# carcomputer_split3_bottom1.net
KiCad netlist of a schematic drawn in EAGLE
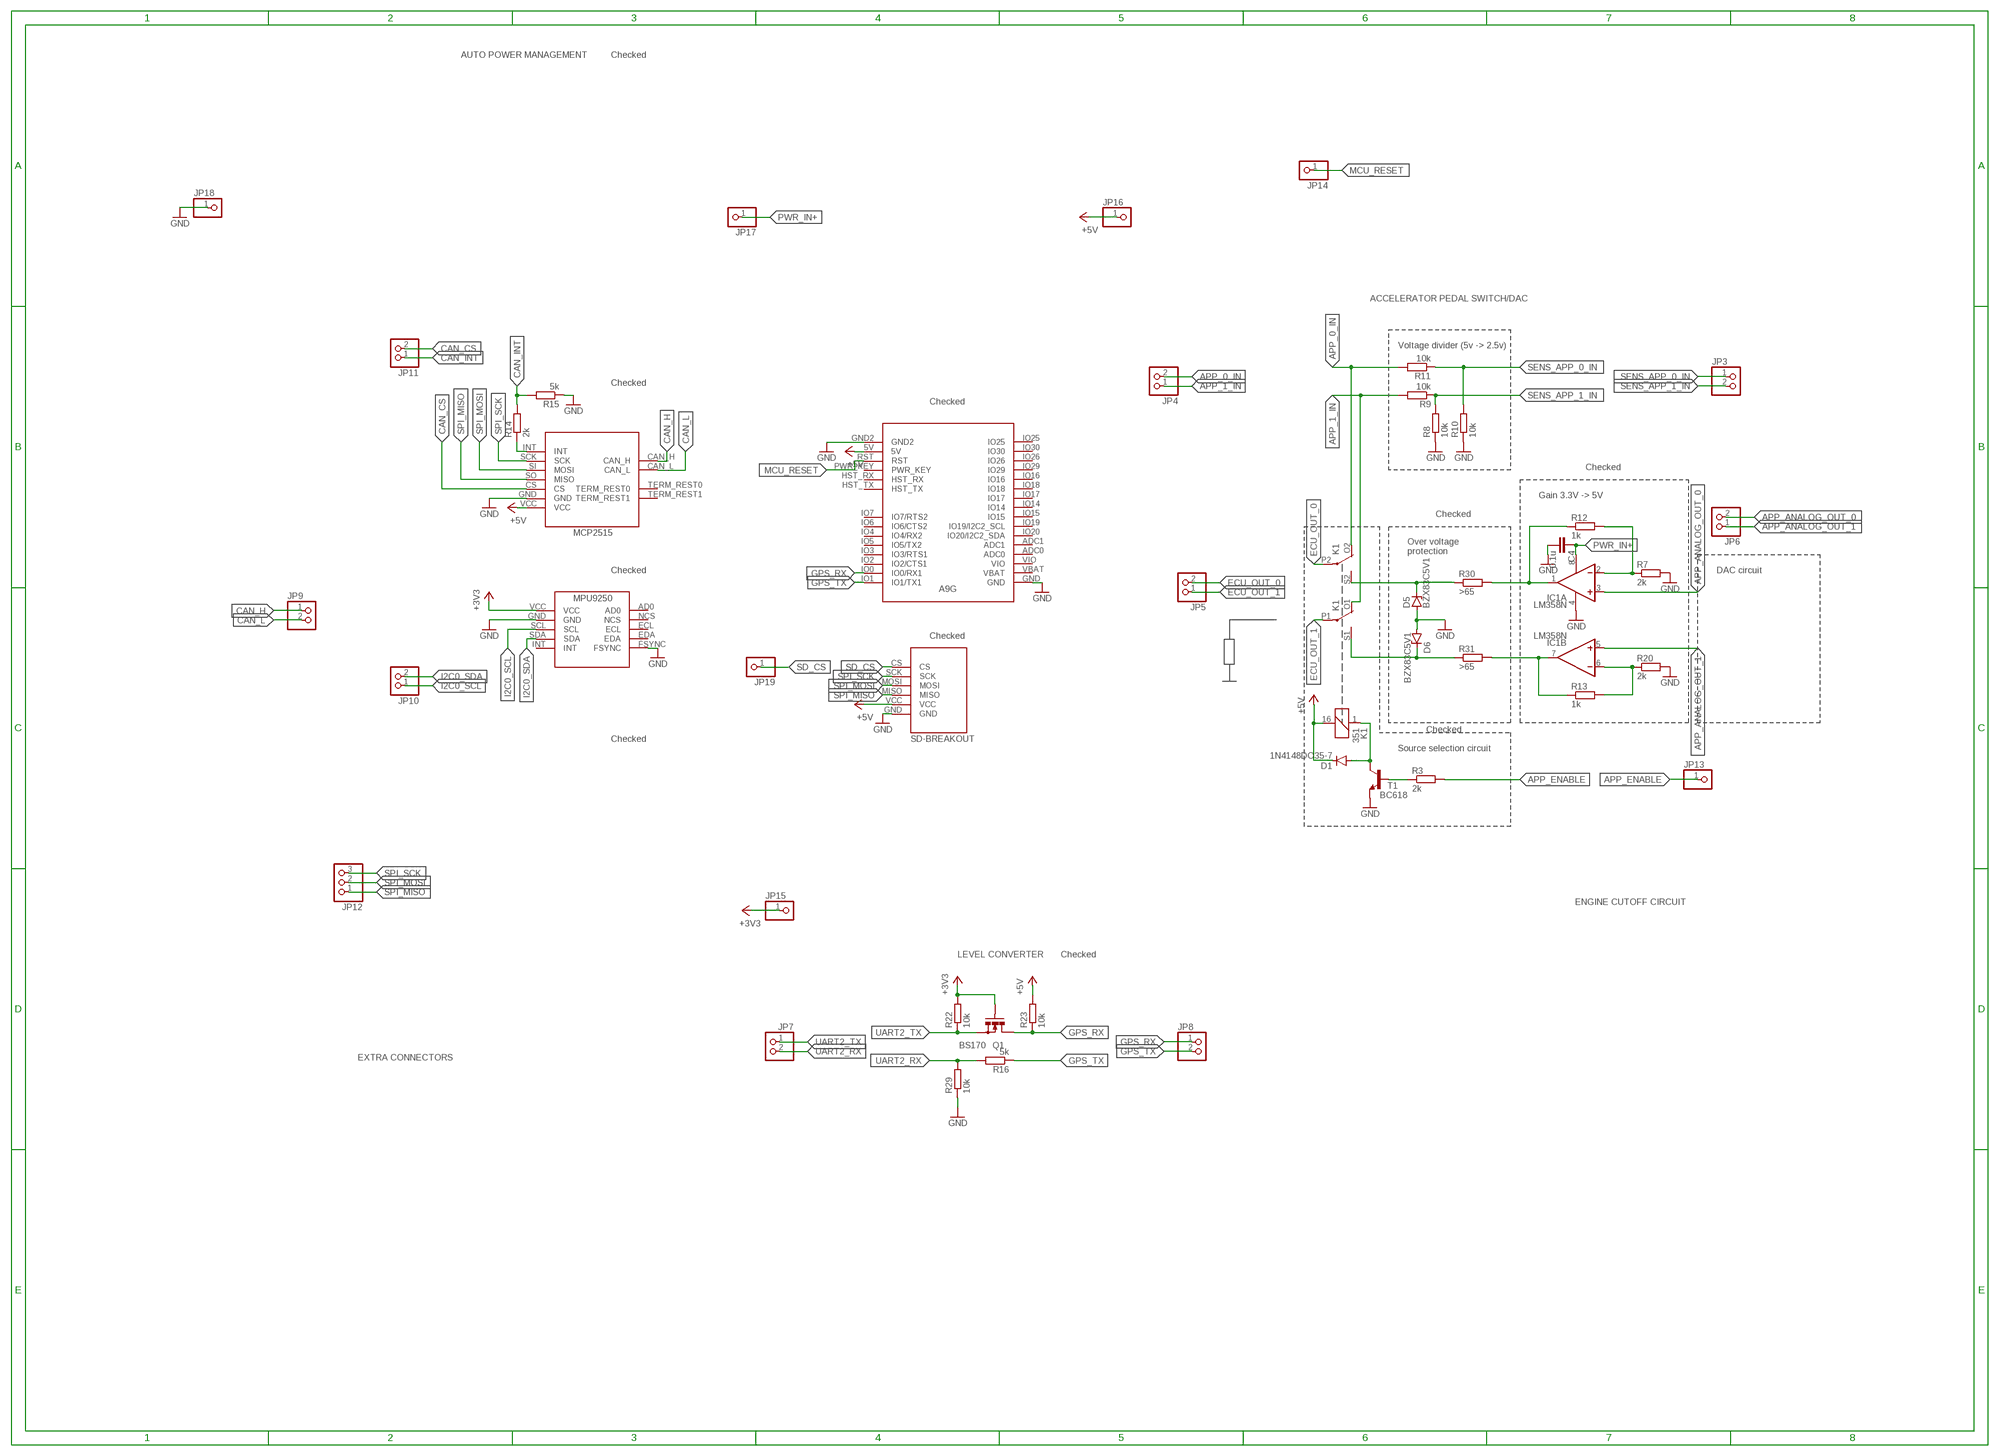
[diagram p0: schematic, sheet 1]

(export (version "E")
  (design (tool "Eeschema 10.0.6"))
  (components
    (comp (ref "C4")
      (value "0.1u")
      (footprint "eagle-import:C025-050X050")
      (libsource (lib "eagle-import") (part "C-EU025-050X050"))
    )
    (comp (ref "D1")
      (value "1N4148DO35-7")
      (footprint "eagle-import:DO35-7")
      (libsource (lib "eagle-import") (part "1N4148DO35-7"))
    )
    (comp (ref "D5")
      (value "BZX83C5V1")
      (footprint "eagle-import:DO41Z10")
      (libsource (lib "eagle-import") (part "BZX85"))
    )
    (comp (ref "D6")
      (value "BZX83C5V1")
      (footprint "eagle-import:DO41Z10")
      (libsource (lib "eagle-import") (part "BZX85"))
    )
    (comp (ref "IC1")
      (value "LM358N")
      (footprint "eagle-import:DIL08")
      (libsource (lib "eagle-import") (part "LM358N"))
    )
    (comp (ref "JP3")
      (value "PINHD-1X2")
      (footprint "eagle-import:1X02")
      (libsource (lib "eagle-import") (part "PINHD-1X2"))
    )
    (comp (ref "JP4")
      (value "PINHD-1X2")
      (footprint "eagle-import:1X02")
      (libsource (lib "eagle-import") (part "PINHD-1X2"))
    )
    (comp (ref "JP5")
      (value "PINHD-1X2")
      (footprint "eagle-import:1X02")
      (libsource (lib "eagle-import") (part "PINHD-1X2"))
    )
    (comp (ref "JP6")
      (value "PINHD-1X2")
      (footprint "eagle-import:1X02")
      (libsource (lib "eagle-import") (part "PINHD-1X2"))
    )
    (comp (ref "JP7")
      (value "PINHD-1X2")
      (footprint "eagle-import:1X02")
      (libsource (lib "eagle-import") (part "PINHD-1X2"))
    )
    (comp (ref "JP8")
      (value "PINHD-1X2")
      (footprint "eagle-import:1X02")
      (libsource (lib "eagle-import") (part "PINHD-1X2"))
    )
    (comp (ref "JP9")
      (value "PINHD-1X2")
      (footprint "eagle-import:1X02")
      (libsource (lib "eagle-import") (part "PINHD-1X2"))
    )
    (comp (ref "JP10")
      (value "PINHD-1X2")
      (footprint "eagle-import:1X02")
      (libsource (lib "eagle-import") (part "PINHD-1X2"))
    )
    (comp (ref "JP11")
      (value "PINHD-1X2")
      (footprint "eagle-import:1X02")
      (libsource (lib "eagle-import") (part "PINHD-1X2"))
    )
    (comp (ref "JP12")
      (value "PINHD-1X3")
      (footprint "eagle-import:1X03")
      (libsource (lib "eagle-import") (part "PINHD-1X3"))
    )
    (comp (ref "JP13")
      (value "PINHD-1X1")
      (footprint "eagle-import:1X01")
      (libsource (lib "eagle-import") (part "PINHD-1X1"))
    )
    (comp (ref "JP14")
      (value "PINHD-1X1")
      (footprint "eagle-import:1X01")
      (libsource (lib "eagle-import") (part "PINHD-1X1"))
    )
    (comp (ref "JP15")
      (value "PINHD-1X1")
      (footprint "eagle-import:1X01")
      (libsource (lib "eagle-import") (part "PINHD-1X1"))
    )
    (comp (ref "JP16")
      (value "PINHD-1X1")
      (footprint "eagle-import:1X01")
      (libsource (lib "eagle-import") (part "PINHD-1X1"))
    )
    (comp (ref "JP17")
      (value "PINHD-1X1")
      (footprint "eagle-import:1X01")
      (libsource (lib "eagle-import") (part "PINHD-1X1"))
    )
    (comp (ref "JP18")
      (value "PINHD-1X1")
      (footprint "eagle-import:1X01")
      (libsource (lib "eagle-import") (part "PINHD-1X1"))
    )
    (comp (ref "JP19")
      (value "PINHD-1X1")
      (footprint "eagle-import:1X01")
      (libsource (lib "eagle-import") (part "PINHD-1X1"))
    )
    (comp (ref "K1")
      (value "351")
      (footprint "eagle-import:351")
      (libsource (lib "eagle-import") (part "351"))
    )
    (comp (ref "Q1")
      (value "BS170")
      (footprint "eagle-import:SOT54E")
      (libsource (lib "eagle-import") (part "BS170"))
    )
    (comp (ref "R3")
      (value "2k")
      (footprint "eagle-import:0207_7")
      (libsource (lib "eagle-import") (part "R-EU_0207/7"))
    )
    (comp (ref "R7")
      (value "2k")
      (footprint "eagle-import:0207_7")
      (libsource (lib "eagle-import") (part "R-EU_0207/7"))
    )
    (comp (ref "R8")
      (value "10k")
      (footprint "eagle-import:0207_7")
      (libsource (lib "eagle-import") (part "R-EU_0207/7"))
    )
    (comp (ref "R9")
      (value "10k")
      (footprint "eagle-import:0207_7")
      (libsource (lib "eagle-import") (part "R-EU_0207/7"))
    )
    (comp (ref "R10")
      (value "10k")
      (footprint "eagle-import:0207_7")
      (libsource (lib "eagle-import") (part "R-EU_0207/7"))
    )
    (comp (ref "R11")
      (value "10k")
      (footprint "eagle-import:0207_7")
      (libsource (lib "eagle-import") (part "R-EU_0207/7"))
    )
    (comp (ref "R12")
      (value "1k")
      (footprint "eagle-import:0207_7")
      (libsource (lib "eagle-import") (part "R-EU_0207/7"))
    )
    (comp (ref "R13")
      (value "1k")
      (footprint "eagle-import:0207_7")
      (libsource (lib "eagle-import") (part "R-EU_0207/7"))
    )
    (comp (ref "R14")
      (value "2k")
      (footprint "eagle-import:0207_7")
      (libsource (lib "eagle-import") (part "R-EU_0207/7"))
    )
    (comp (ref "R15")
      (value "5k")
      (footprint "eagle-import:0207_7")
      (libsource (lib "eagle-import") (part "R-EU_0207/7"))
    )
    (comp (ref "R16")
      (value "5k")
      (footprint "eagle-import:0207_7")
      (libsource (lib "eagle-import") (part "R-EU_0207/7"))
    )
    (comp (ref "R20")
      (value "2k")
      (footprint "eagle-import:0207_7")
      (libsource (lib "eagle-import") (part "R-EU_0207/7"))
    )
    (comp (ref "R22")
      (value "10k")
      (footprint "eagle-import:0207_7")
      (libsource (lib "eagle-import") (part "R-EU_0207/7"))
    )
    (comp (ref "R23")
      (value "10k")
      (footprint "eagle-import:0207_7")
      (libsource (lib "eagle-import") (part "R-EU_0207/7"))
    )
    (comp (ref "R29")
      (value "10k")
      (footprint "eagle-import:0207_7")
      (libsource (lib "eagle-import") (part "R-EU_0207/7"))
    )
    (comp (ref "R30")
      (value ">65")
      (footprint "eagle-import:0207_7")
      (libsource (lib "eagle-import") (part "R-EU_0207/7"))
    )
    (comp (ref "R31")
      (value ">65")
      (footprint "eagle-import:0207_7")
      (libsource (lib "eagle-import") (part "R-EU_0207/7"))
    )
    (comp (ref "T1")
      (value "BC618")
      (footprint "eagle-import:TO92-EBC")
      (libsource (lib "eagle-import") (part "BC618"))
    )
    (comp (ref "U$2")
      (value "MCP2515_DEVBOARDINVERTED")
      (footprint "eagle-import:MCP2515_DEVBOARD_INVERTED")
      (libsource (lib "eagle-import") (part "MCP2515_DEVBOARDINVERTED"))
    )
    (comp (ref "U$3")
      (value "MPU9250_BREAKOUT")
      (footprint "eagle-import:MPU9250_BREAKOUT")
      (libsource (lib "eagle-import") (part "MPU9250_BREAKOUT"))
    )
    (comp (ref "U$5")
      (value "HKD-MICRO-SD-BREAKOUT")
      (footprint "eagle-import:HKD-MICRO-SD-BREAKOUT")
      (libsource (lib "eagle-import") (part "HKD-MICRO-SD-BREAKOUT"))
    )
    (comp (ref "U$6")
      (value "A9G")
      (footprint "eagle-import:A9G")
      (libsource (lib "eagle-import") (part "A9G"))
    )
  )
  (nets
    (net (code "1") (name "+3V3") (class "Default")
      (node (ref "JP15") (pin "1") (pinfunction "1_1") (pintype "passive"))
      (node (ref "Q1") (pin "G") (pinfunction "G_G") (pintype "passive"))
      (node (ref "R22") (pin "2") (pinfunction "2_2") (pintype "passive"))
      (node (ref "U$3") (pin "VCC") (pinfunction "VCC_VCC") (pintype "bidirectional"))
    )
    (net (code "2") (name "+5V") (class "Default")
      (node (ref "D1") (pin "C") (pinfunction "C_C") (pintype "passive"))
      (node (ref "JP16") (pin "1") (pinfunction "1_1") (pintype "passive"))
      (node (ref "K1") (pin "16") (pinfunction "2_16") (pintype "passive"))
      (node (ref "R23") (pin "2") (pinfunction "2_2") (pintype "passive"))
      (node (ref "U$2") (pin "VCC") (pinfunction "VCC_VCC") (pintype "bidirectional"))
      (node (ref "U$5") (pin "VCC") (pinfunction "VCC_VCC") (pintype "bidirectional"))
      (node (ref "U$6") (pin "5V") (pinfunction "5V_5V") (pintype "bidirectional"))
    )
    (net (code "3") (name "APP_0_IN") (class "Default")
      (node (ref "JP4") (pin "2") (pinfunction "2_2") (pintype "passive"))
      (node (ref "K1") (pin "O2") (pinfunction "O_O2") (pintype "passive"))
      (node (ref "R11") (pin "2") (pinfunction "2_2") (pintype "passive"))
    )
    (net (code "4") (name "APP_1_IN") (class "Default")
      (node (ref "JP4") (pin "1") (pinfunction "1_1") (pintype "passive"))
      (node (ref "K1") (pin "O1") (pinfunction "O_O1") (pintype "passive"))
      (node (ref "R9") (pin "2") (pinfunction "2_2") (pintype "passive"))
    )
    (net (code "5") (name "APP_ANALOG_OUT_0") (class "Default")
      (node (ref "IC1") (pin "3") (pinfunction "+IN_3") (pintype "input"))
      (node (ref "JP6") (pin "2") (pinfunction "2_2") (pintype "passive"))
    )
    (net (code "6") (name "APP_ANALOG_OUT_1") (class "Default")
      (node (ref "IC1") (pin "5") (pinfunction "+IN_5") (pintype "input"))
      (node (ref "JP6") (pin "1") (pinfunction "1_1") (pintype "passive"))
    )
    (net (code "7") (name "APP_ENABLE") (class "Default")
      (node (ref "JP13") (pin "1") (pinfunction "1_1") (pintype "passive"))
      (node (ref "R3") (pin "2") (pinfunction "2_2") (pintype "passive"))
    )
    (net (code "8") (name "CAN_CS") (class "Default")
      (node (ref "JP11") (pin "2") (pinfunction "2_2") (pintype "passive"))
      (node (ref "U$2") (pin "CS") (pinfunction "CS_CS") (pintype "input"))
    )
    (net (code "9") (name "CAN_H") (class "Default")
      (node (ref "JP9") (pin "1") (pinfunction "1_1") (pintype "passive"))
      (node (ref "U$2") (pin "CAN_H") (pinfunction "CAN_H_CAN_H") (pintype "bidirectional"))
    )
    (net (code "10") (name "CAN_INT") (class "Default")
      (node (ref "JP11") (pin "1") (pinfunction "1_1") (pintype "passive"))
      (node (ref "R14") (pin "2") (pinfunction "2_2") (pintype "passive"))
      (node (ref "R15") (pin "2") (pinfunction "2_2") (pintype "passive"))
    )
    (net (code "11") (name "CAN_L") (class "Default")
      (node (ref "JP9") (pin "2") (pinfunction "2_2") (pintype "passive"))
      (node (ref "U$2") (pin "CAN_L") (pinfunction "CAN_L_CAN_L") (pintype "bidirectional"))
    )
    (net (code "12") (name "ECU_OUT_0") (class "Default")
      (node (ref "JP5") (pin "2") (pinfunction "2_2") (pintype "passive"))
      (node (ref "K1") (pin "P2") (pinfunction "P_P2") (pintype "passive"))
    )
    (net (code "13") (name "ECU_OUT_1") (class "Default")
      (node (ref "JP5") (pin "1") (pinfunction "1_1") (pintype "passive"))
      (node (ref "K1") (pin "P1") (pinfunction "P_P1") (pintype "passive"))
    )
    (net (code "14") (name "GND") (class "Default")
      (node (ref "C4") (pin "2") (pinfunction "2_2") (pintype "passive"))
      (node (ref "D5") (pin "A") (pinfunction "A_A") (pintype "passive"))
      (node (ref "D6") (pin "A") (pinfunction "A_A") (pintype "passive"))
      (node (ref "IC1") (pin "4") (pinfunction "V-_4") (pintype "power_in"))
      (node (ref "JP18") (pin "1") (pinfunction "1_1") (pintype "passive"))
      (node (ref "R10") (pin "1") (pinfunction "1_1") (pintype "passive"))
      (node (ref "R15") (pin "1") (pinfunction "1_1") (pintype "passive"))
      (node (ref "R20") (pin "2") (pinfunction "2_2") (pintype "passive"))
      (node (ref "R29") (pin "1") (pinfunction "1_1") (pintype "passive"))
      (node (ref "R7") (pin "2") (pinfunction "2_2") (pintype "passive"))
      (node (ref "R8") (pin "1") (pinfunction "1_1") (pintype "passive"))
      (node (ref "T1") (pin "E") (pinfunction "E_E") (pintype "passive"))
      (node (ref "U$2") (pin "GND") (pinfunction "GND_GND") (pintype "bidirectional"))
      (node (ref "U$3") (pin "FSYNC") (pinfunction "FSYNC_FSYNC") (pintype "bidirectional"))
      (node (ref "U$3") (pin "GND") (pinfunction "GND_GND") (pintype "bidirectional"))
      (node (ref "U$5") (pin "GND") (pinfunction "GND_GND") (pintype "bidirectional"))
      (node (ref "U$6") (pin "GND") (pinfunction "GND_GND") (pintype "bidirectional"))
      (node (ref "U$6") (pin "GND2") (pinfunction "GND2_GND2") (pintype "bidirectional"))
    )
    (net (code "15") (name "GPS_RX") (class "Default")
      (node (ref "JP8") (pin "1") (pinfunction "1_1") (pintype "passive"))
      (node (ref "Q1") (pin "D") (pinfunction "D_D") (pintype "passive"))
      (node (ref "R23") (pin "1") (pinfunction "1_1") (pintype "passive"))
      (node (ref "U$6") (pin "IO0") (pinfunction "IO0/RX1_IO0") (pintype "bidirectional"))
    )
    (net (code "16") (name "GPS_TX") (class "Default")
      (node (ref "JP8") (pin "2") (pinfunction "2_2") (pintype "passive"))
      (node (ref "R16") (pin "1") (pinfunction "1_1") (pintype "passive"))
      (node (ref "U$6") (pin "IO1") (pinfunction "IO1/TX1_IO1") (pintype "bidirectional"))
    )
    (net (code "17") (name "I2C0_SCL") (class "Default")
      (node (ref "JP10") (pin "1") (pinfunction "1_1") (pintype "passive"))
      (node (ref "U$3") (pin "SCL") (pinfunction "SCL_SCL") (pintype "bidirectional"))
    )
    (net (code "18") (name "I2C0_SDA") (class "Default")
      (node (ref "JP10") (pin "2") (pinfunction "2_2") (pintype "passive"))
      (node (ref "U$3") (pin "SDA") (pinfunction "SDA_SDA") (pintype "bidirectional"))
    )
    (net (code "19") (name "MCU_RESET") (class "Default")
      (node (ref "JP14") (pin "1") (pinfunction "1_1") (pintype "passive"))
      (node (ref "U$6") (pin "RST") (pinfunction "RST_RST") (pintype "bidirectional"))
    )
    (net (code "20") (name "Net-(D1-PadA)") (class "Default")
      (node (ref "D1") (pin "A") (pinfunction "A_A") (pintype "passive"))
      (node (ref "K1") (pin "1") (pinfunction "1_1") (pintype "passive"))
      (node (ref "T1") (pin "C") (pinfunction "C_C") (pintype "passive"))
    )
    (net (code "21") (name "Net-(IC1A--IN)") (class "Default")
      (node (ref "IC1") (pin "2") (pinfunction "-IN_2") (pintype "input"))
      (node (ref "R12") (pin "2") (pinfunction "2_2") (pintype "passive"))
      (node (ref "R7") (pin "1") (pinfunction "1_1") (pintype "passive"))
    )
    (net (code "22") (name "Net-(IC1A-OUT)") (class "Default")
      (node (ref "IC1") (pin "1") (pinfunction "OUT_1") (pintype "output"))
      (node (ref "R12") (pin "1") (pinfunction "1_1") (pintype "passive"))
      (node (ref "R30") (pin "2") (pinfunction "2_2") (pintype "passive"))
    )
    (net (code "23") (name "Net-(IC1B--IN)") (class "Default")
      (node (ref "IC1") (pin "6") (pinfunction "-IN_6") (pintype "input"))
      (node (ref "R13") (pin "2") (pinfunction "2_2") (pintype "passive"))
      (node (ref "R20") (pin "1") (pinfunction "1_1") (pintype "passive"))
    )
    (net (code "24") (name "Net-(IC1B-OUT)") (class "Default")
      (node (ref "IC1") (pin "7") (pinfunction "OUT_7") (pintype "output"))
      (node (ref "R13") (pin "1") (pinfunction "1_1") (pintype "passive"))
      (node (ref "R31") (pin "2") (pinfunction "2_2") (pintype "passive"))
    )
    (net (code "25") (name "Net-(K1B-S)") (class "Default")
      (node (ref "D6") (pin "C") (pinfunction "C_C") (pintype "passive"))
      (node (ref "K1") (pin "S1") (pinfunction "S_S1") (pintype "passive"))
      (node (ref "R31") (pin "1") (pinfunction "1_1") (pintype "passive"))
    )
    (net (code "26") (name "Net-(K1C-S)") (class "Default")
      (node (ref "D5") (pin "C") (pinfunction "C_C") (pintype "passive"))
      (node (ref "K1") (pin "S2") (pinfunction "S_S2") (pintype "passive"))
      (node (ref "R30") (pin "1") (pinfunction "1_1") (pintype "passive"))
    )
    (net (code "27") (name "Net-(R3-Pad1)") (class "Default")
      (node (ref "R3") (pin "1") (pinfunction "1_1") (pintype "passive"))
      (node (ref "T1") (pin "B") (pinfunction "B_B") (pintype "passive"))
    )
    (net (code "28") (name "Net-(R14-Pad1)") (class "Default")
      (node (ref "R14") (pin "1") (pinfunction "1_1") (pintype "passive"))
      (node (ref "U$2") (pin "INT") (pinfunction "INT_INT") (pintype "output"))
    )
    (net (code "29") (name "PWR_IN+") (class "Default")
      (node (ref "C4") (pin "1") (pinfunction "1_1") (pintype "passive"))
      (node (ref "IC1") (pin "8") (pinfunction "V+_8") (pintype "power_in"))
      (node (ref "JP17") (pin "1") (pinfunction "1_1") (pintype "passive"))
    )
    (net (code "30") (name "SD_CS") (class "Default")
      (node (ref "JP19") (pin "1") (pinfunction "1_1") (pintype "passive"))
      (node (ref "U$5") (pin "CS") (pinfunction "CS_CS") (pintype "bidirectional"))
    )
    (net (code "31") (name "SENS_APP_0_IN") (class "Default")
      (node (ref "JP3") (pin "1") (pinfunction "1_1") (pintype "passive"))
      (node (ref "R10") (pin "2") (pinfunction "2_2") (pintype "passive"))
      (node (ref "R11") (pin "1") (pinfunction "1_1") (pintype "passive"))
    )
    (net (code "32") (name "SENS_APP_1_IN") (class "Default")
      (node (ref "JP3") (pin "2") (pinfunction "2_2") (pintype "passive"))
      (node (ref "R8") (pin "2") (pinfunction "2_2") (pintype "passive"))
      (node (ref "R9") (pin "1") (pinfunction "1_1") (pintype "passive"))
    )
    (net (code "33") (name "SPI_MISO") (class "Default")
      (node (ref "JP12") (pin "1") (pinfunction "1_1") (pintype "passive"))
      (node (ref "U$2") (pin "SO") (pinfunction "MISO_SO") (pintype "output"))
      (node (ref "U$5") (pin "MISO") (pinfunction "MISO_MISO") (pintype "bidirectional"))
    )
    (net (code "34") (name "SPI_MOSI") (class "Default")
      (node (ref "JP12") (pin "2") (pinfunction "2_2") (pintype "passive"))
      (node (ref "U$2") (pin "SI") (pinfunction "MOSI_SI") (pintype "input"))
      (node (ref "U$5") (pin "MOSI") (pinfunction "MOSI_MOSI") (pintype "bidirectional"))
    )
    (net (code "35") (name "SPI_SCK") (class "Default")
      (node (ref "JP12") (pin "3") (pinfunction "3_3") (pintype "passive"))
      (node (ref "U$2") (pin "SCK") (pinfunction "SCK_SCK") (pintype "input"))
      (node (ref "U$5") (pin "SCK") (pinfunction "SCK_SCK") (pintype "bidirectional"))
    )
    (net (code "36") (name "UART2_RX") (class "Default")
      (node (ref "JP7") (pin "2") (pinfunction "2_2") (pintype "passive"))
      (node (ref "R16") (pin "2") (pinfunction "2_2") (pintype "passive"))
      (node (ref "R29") (pin "2") (pinfunction "2_2") (pintype "passive"))
    )
    (net (code "37") (name "UART2_TX") (class "Default")
      (node (ref "JP7") (pin "1") (pinfunction "1_1") (pintype "passive"))
      (node (ref "Q1") (pin "S") (pinfunction "S_S") (pintype "passive"))
      (node (ref "R22") (pin "1") (pinfunction "1_1") (pintype "passive"))
    )
    (net (code "38") (name "unconnected-(U$2-PadTERM_REST0)") (class "Default")
      (node (ref "U$2") (pin "TERM_REST0") (pinfunction "TERM_REST0_TERM_REST0") (pintype "bidirectional"))
    )
    (net (code "39") (name "unconnected-(U$2-PadTERM_REST1)") (class "Default")
      (node (ref "U$2") (pin "TERM_REST1") (pinfunction "TERM_REST1_TERM_REST1") (pintype "bidirectional"))
    )
    (net (code "40") (name "unconnected-(U$3-PadAD0)") (class "Default")
      (node (ref "U$3") (pin "AD0") (pinfunction "AD0_AD0") (pintype "bidirectional"))
    )
    (net (code "41") (name "unconnected-(U$3-PadECL)") (class "Default")
      (node (ref "U$3") (pin "ECL") (pinfunction "ECL_ECL") (pintype "bidirectional"))
    )
    (net (code "42") (name "unconnected-(U$3-PadEDA)") (class "Default")
      (node (ref "U$3") (pin "EDA") (pinfunction "EDA_EDA") (pintype "bidirectional"))
    )
    (net (code "43") (name "unconnected-(U$3-PadINT)") (class "Default")
      (node (ref "U$3") (pin "INT") (pinfunction "INT_INT") (pintype "bidirectional"))
    )
    (net (code "44") (name "unconnected-(U$3-PadNCS)") (class "Default")
      (node (ref "U$3") (pin "NCS") (pinfunction "NCS_NCS") (pintype "bidirectional"))
    )
    (net (code "45") (name "unconnected-(U$6-IO2{slash}CTS1-PadIO2)") (class "Default")
      (node (ref "U$6") (pin "IO2") (pinfunction "IO2/CTS1_IO2") (pintype "bidirectional"))
    )
    (net (code "46") (name "unconnected-(U$6-IO3{slash}RTS1-PadIO3)") (class "Default")
      (node (ref "U$6") (pin "IO3") (pinfunction "IO3/RTS1_IO3") (pintype "bidirectional"))
    )
    (net (code "47") (name "unconnected-(U$6-IO4{slash}RX2-PadIO4)") (class "Default")
      (node (ref "U$6") (pin "IO4") (pinfunction "IO4/RX2_IO4") (pintype "bidirectional"))
    )
    (net (code "48") (name "unconnected-(U$6-IO5{slash}TX2-PadIO5)") (class "Default")
      (node (ref "U$6") (pin "IO5") (pinfunction "IO5/TX2_IO5") (pintype "bidirectional"))
    )
    (net (code "49") (name "unconnected-(U$6-IO6{slash}CTS2-PadIO6)") (class "Default")
      (node (ref "U$6") (pin "IO6") (pinfunction "IO6/CTS2_IO6") (pintype "bidirectional"))
    )
    (net (code "50") (name "unconnected-(U$6-IO7{slash}RTS2-PadIO7)") (class "Default")
      (node (ref "U$6") (pin "IO7") (pinfunction "IO7/RTS2_IO7") (pintype "bidirectional"))
    )
    (net (code "51") (name "unconnected-(U$6-IO19{slash}I2C2_SCL-PadIO19)") (class "Default")
      (node (ref "U$6") (pin "IO19") (pinfunction "IO19/I2C2_SCL_IO19") (pintype "bidirectional"))
    )
    (net (code "52") (name "unconnected-(U$6-IO20{slash}I2C2_SDA-PadIO20)") (class "Default")
      (node (ref "U$6") (pin "IO20") (pinfunction "IO20/I2C2_SDA_IO20") (pintype "bidirectional"))
    )
    (net (code "53") (name "unconnected-(U$6-PadADC0)") (class "Default")
      (node (ref "U$6") (pin "ADC0") (pinfunction "ADC0_ADC0") (pintype "bidirectional"))
    )
    (net (code "54") (name "unconnected-(U$6-PadADC1)") (class "Default")
      (node (ref "U$6") (pin "ADC1") (pinfunction "ADC1_ADC1") (pintype "bidirectional"))
    )
    (net (code "55") (name "unconnected-(U$6-PadHST_RX)") (class "Default")
      (node (ref "U$6") (pin "HST_RX") (pinfunction "HST_RX_HST_RX") (pintype "bidirectional"))
    )
    (net (code "56") (name "unconnected-(U$6-PadHST_TX)") (class "Default")
      (node (ref "U$6") (pin "HST_TX") (pinfunction "HST_TX_HST_TX") (pintype "bidirectional"))
    )
    (net (code "57") (name "unconnected-(U$6-PadIO14)") (class "Default")
      (node (ref "U$6") (pin "IO14") (pinfunction "IO14_IO14") (pintype "bidirectional"))
    )
    (net (code "58") (name "unconnected-(U$6-PadIO15)") (class "Default")
      (node (ref "U$6") (pin "IO15") (pinfunction "IO15_IO15") (pintype "bidirectional"))
    )
    (net (code "59") (name "unconnected-(U$6-PadIO16)") (class "Default")
      (node (ref "U$6") (pin "IO16") (pinfunction "IO16_IO16") (pintype "bidirectional"))
    )
    (net (code "60") (name "unconnected-(U$6-PadIO17)") (class "Default")
      (node (ref "U$6") (pin "IO17") (pinfunction "IO17_IO17") (pintype "bidirectional"))
    )
    (net (code "61") (name "unconnected-(U$6-PadIO18)") (class "Default")
      (node (ref "U$6") (pin "IO18") (pinfunction "IO18_IO18") (pintype "bidirectional"))
    )
    (net (code "62") (name "unconnected-(U$6-PadIO25)") (class "Default")
      (node (ref "U$6") (pin "IO25") (pinfunction "IO25_IO25") (pintype "bidirectional"))
    )
    (net (code "63") (name "unconnected-(U$6-PadIO26)") (class "Default")
      (node (ref "U$6") (pin "IO26") (pinfunction "IO26_IO26") (pintype "bidirectional"))
    )
    (net (code "64") (name "unconnected-(U$6-PadIO29)") (class "Default")
      (node (ref "U$6") (pin "IO29") (pinfunction "IO29_IO29") (pintype "bidirectional"))
    )
    (net (code "65") (name "unconnected-(U$6-PadIO30)") (class "Default")
      (node (ref "U$6") (pin "IO30") (pinfunction "IO30_IO30") (pintype "bidirectional"))
    )
    (net (code "66") (name "unconnected-(U$6-PadPWR_KEY)") (class "Default")
      (node (ref "U$6") (pin "PWR_KEY") (pinfunction "PWR_KEY_PWR_KEY") (pintype "bidirectional"))
    )
    (net (code "67") (name "unconnected-(U$6-PadVBAT)") (class "Default")
      (node (ref "U$6") (pin "VBAT") (pinfunction "VBAT_VBAT") (pintype "bidirectional"))
    )
    (net (code "68") (name "unconnected-(U$6-PadVIO)") (class "Default")
      (node (ref "U$6") (pin "VIO") (pinfunction "VIO_VIO") (pintype "bidirectional"))
    )
  )
)
